# interface-switches.net
KiCad netlist of a schematic drawn in Altium Designer
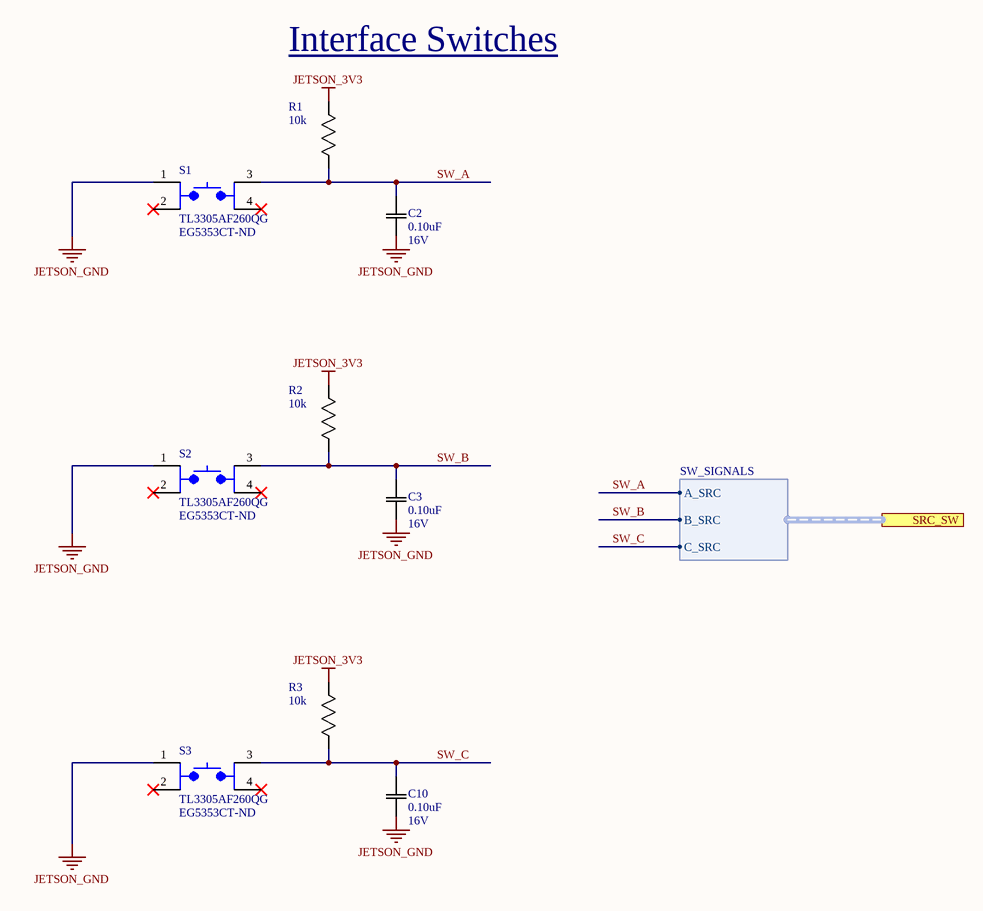
[diagram p0: interface-switches.SchDoc]

(export (version "E")
  (design (tool "Eeschema 10.0.6"))
  (components
    (comp (ref "C2")
      (value "0.10uF")
      (footprint "0603")
      (description "CAP CER 0.10UF 16V X5R 0603")
      (fields
        (field (name "TOLERANCE") "10%")
        (field (name "RATING") "16V")
        (field (name "PART NUMBER") "CAP 0.10uF 16V")
      )
      (libsource (lib "capacitor_library") (part "CAP 0.10uF 16V"))
    )
    (comp (ref "C3")
      (value "0.10uF")
      (footprint "0603")
      (description "CAP CER 0.10UF 16V X5R 0603")
      (fields
        (field (name "TOLERANCE") "10%")
        (field (name "RATING") "16V")
        (field (name "PART NUMBER") "CAP 0.10uF 16V")
      )
      (libsource (lib "capacitor_library") (part "CAP 0.10uF 16V"))
    )
    (comp (ref "C10")
      (value "0.10uF")
      (footprint "0603")
      (description "CAP CER 0.10UF 16V X5R 0603")
      (fields
        (field (name "TOLERANCE") "10%")
        (field (name "RATING") "16V")
        (field (name "PART NUMBER") "CAP 0.10uF 16V")
      )
      (libsource (lib "capacitor_library") (part "CAP 0.10uF 16V"))
    )
    (comp (ref "R1")
      (value "10k")
      (footprint "0603")
      (description "RES SMD 10K OHM 5% 1/8W 0805")
      (fields (field (name "TOLERANCE") "5%") (field (name "PART NUMBER") "RES 10k 1/8W - 5%"))
      (libsource (lib "Resistor_Library") (part "RES 10k 1/8W 5%"))
    )
    (comp (ref "R2")
      (value "10k")
      (footprint "0603")
      (description "RES SMD 10K OHM 5% 1/8W 0805")
      (fields (field (name "TOLERANCE") "5%") (field (name "PART NUMBER") "RES 10k 1/8W - 5%"))
      (libsource (lib "Resistor_Library") (part "RES 10k 1/8W 5%"))
    )
    (comp (ref "R3")
      (value "10k")
      (footprint "0603")
      (description "RES SMD 10K OHM 5% 1/8W 0805")
      (fields (field (name "TOLERANCE") "5%") (field (name "PART NUMBER") "RES 10k 1/8W - 5%"))
      (libsource (lib "Resistor_Library") (part "RES 10k 1/8W 5%"))
    )
    (comp (ref "S1")
      (value "TL3305AF260QG")
      (footprint "SW_TL3305AF260QG")
      (description "Tactile Switch SPST-NO Top Actuated Surface Mount")
      (fields
        (field (name "MF") "E-Switch")
        (field (name "SUPPLIER PART NUMBER 1") "EG5353CT-ND")
        (field (name "PART NUMBER") "SW PUSH SMD")
      )
      (libsource (lib "Switch_Library") (part "SW PUSH SMD"))
    )
    (comp (ref "S2")
      (value "TL3305AF260QG")
      (footprint "SW_TL3305AF260QG")
      (description "Tactile Switch SPST-NO Top Actuated Surface Mount")
      (fields
        (field (name "MF") "E-Switch")
        (field (name "SUPPLIER PART NUMBER 1") "EG5353CT-ND")
        (field (name "PART NUMBER") "SW PUSH SMD")
      )
      (libsource (lib "Switch_Library") (part "SW PUSH SMD"))
    )
    (comp (ref "S3")
      (value "TL3305AF260QG")
      (footprint "SW_TL3305AF260QG")
      (description "Tactile Switch SPST-NO Top Actuated Surface Mount")
      (fields
        (field (name "MF") "E-Switch")
        (field (name "SUPPLIER PART NUMBER 1") "EG5353CT-ND")
        (field (name "PART NUMBER") "SW PUSH SMD")
      )
      (libsource (lib "Switch_Library") (part "SW PUSH SMD"))
    )
  )
  (nets
    (net (code "2") (name "/SW_A") (class "Default")
      (node (ref "C2") (pin "2") (pinfunction "C2_2") (pintype "passive"))
      (node (ref "R1") (pin "2") (pinfunction "R2_2") (pintype "passive"))
      (node (ref "S1") (pin "3") (pinfunction "3_3") (pintype "passive"))
    )
    (net (code "3") (name "/SW_B") (class "Default")
      (node (ref "C3") (pin "2") (pinfunction "C2_2") (pintype "passive"))
      (node (ref "R2") (pin "2") (pinfunction "R2_2") (pintype "passive"))
      (node (ref "S2") (pin "3") (pinfunction "3_3") (pintype "passive"))
    )
    (net (code "4") (name "/SW_C") (class "Default")
      (node (ref "C10") (pin "2") (pinfunction "C2_2") (pintype "passive"))
      (node (ref "R3") (pin "2") (pinfunction "R2_2") (pintype "passive"))
      (node (ref "S3") (pin "3") (pinfunction "3_3") (pintype "passive"))
    )
    (net (code "6") (name "JETSON_3V3") (class "Default")
      (node (ref "R1") (pin "1") (pinfunction "R1_1") (pintype "passive"))
      (node (ref "R2") (pin "1") (pinfunction "R1_1") (pintype "passive"))
      (node (ref "R3") (pin "1") (pinfunction "R1_1") (pintype "passive"))
    )
    (net (code "7") (name "JETSON_GND") (class "Default")
      (node (ref "C10") (pin "1") (pinfunction "C1_1") (pintype "passive"))
      (node (ref "C2") (pin "1") (pinfunction "C1_1") (pintype "passive"))
      (node (ref "C3") (pin "1") (pinfunction "C1_1") (pintype "passive"))
      (node (ref "S1") (pin "1") (pinfunction "1_1") (pintype "passive"))
      (node (ref "S2") (pin "1") (pinfunction "1_1") (pintype "passive"))
      (node (ref "S3") (pin "1") (pinfunction "1_1") (pintype "passive"))
    )
    (net (code "8") (name "unconnected-(S1-Pad2)") (class "Default")
      (node (ref "S1") (pin "2") (pinfunction "2_2") (pintype "passive+no_connect"))
    )
    (net (code "9") (name "unconnected-(S1-Pad4)") (class "Default")
      (node (ref "S1") (pin "4") (pinfunction "4_4") (pintype "passive+no_connect"))
    )
    (net (code "10") (name "unconnected-(S2-Pad2)") (class "Default")
      (node (ref "S2") (pin "2") (pinfunction "2_2") (pintype "passive+no_connect"))
    )
    (net (code "11") (name "unconnected-(S2-Pad4)") (class "Default")
      (node (ref "S2") (pin "4") (pinfunction "4_4") (pintype "passive+no_connect"))
    )
    (net (code "12") (name "unconnected-(S3-Pad2)") (class "Default")
      (node (ref "S3") (pin "2") (pinfunction "2_2") (pintype "passive+no_connect"))
    )
    (net (code "13") (name "unconnected-(S3-Pad4)") (class "Default")
      (node (ref "S3") (pin "4") (pinfunction "4_4") (pintype "passive+no_connect"))
    )
  )
)
